# quad_probability_gate.net
KiCad netlist of a schematic drawn in EAGLE
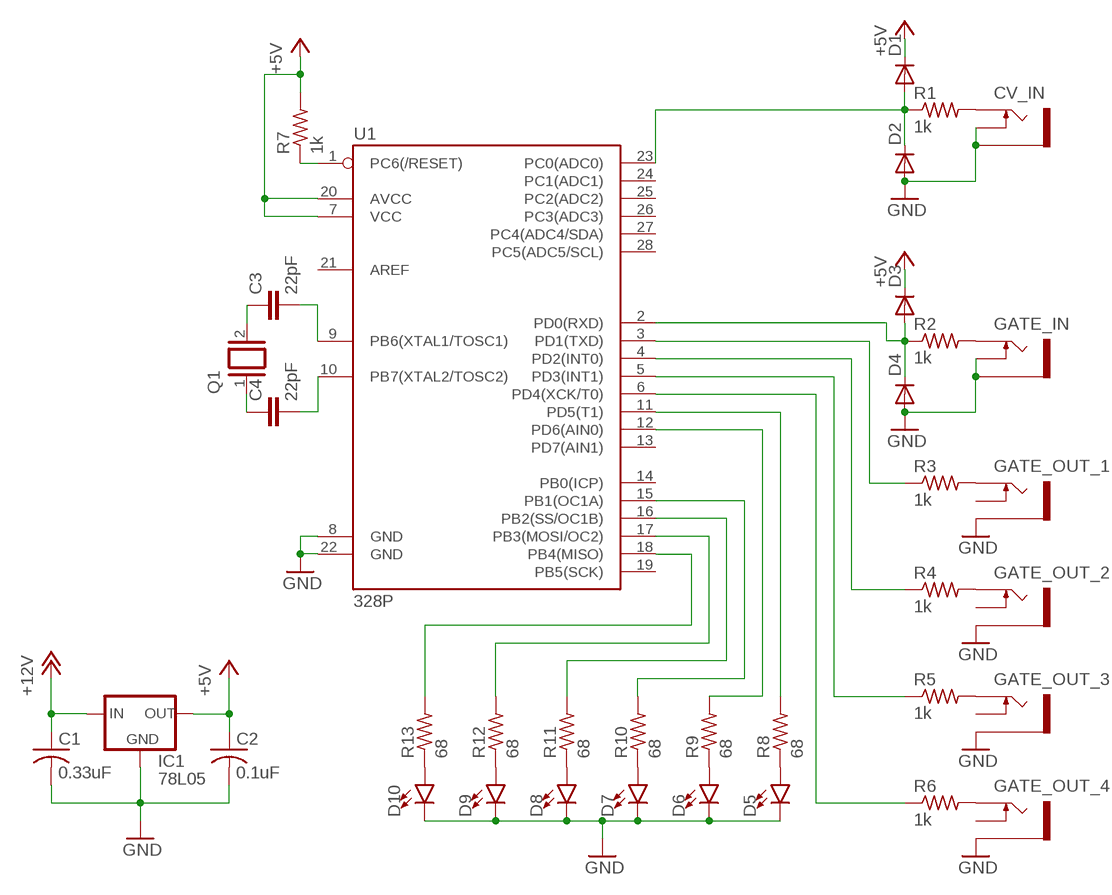
[diagram p0: schematic, sheet 1]

(export (version "E")
  (design (tool "Eeschema 10.0.6"))
  (components
    (comp (ref "C1")
      (value "0.33uF")
      (footprint "eagle-import:C025-024X044")
      (libsource (lib "eagle-import") (part "C-US025-024X044"))
    )
    (comp (ref "C2")
      (value "0.1uF")
      (footprint "eagle-import:C025-024X044")
      (libsource (lib "eagle-import") (part "C-US025-024X044"))
    )
    (comp (ref "C3")
      (value "22pF")
      (footprint "eagle-import:0603")
      (libsource (lib "eagle-import") (part "22PF-0603-50V-5%"))
    )
    (comp (ref "C4")
      (value "22pF")
      (footprint "eagle-import:0603")
      (libsource (lib "eagle-import") (part "22PF-0603-50V-5%"))
    )
    (comp (ref "CV_IN")
      (value "THONKICONNOLD")
      (footprint "eagle-import:THONKICONN")
      (libsource (lib "eagle-import") (part "THONKICONNOLD"))
    )
    (comp (ref "D1")
      (value "SMALL_DIODEDO35-7")
      (footprint "eagle-import:DO35-7")
      (libsource (lib "eagle-import") (part "SMALL_DIODEDO35-7"))
    )
    (comp (ref "D2")
      (value "SMALL_DIODEDO35-7")
      (footprint "eagle-import:DO35-7")
      (libsource (lib "eagle-import") (part "SMALL_DIODEDO35-7"))
    )
    (comp (ref "D3")
      (value "SMALL_DIODEDO35-7")
      (footprint "eagle-import:DO35-7")
      (libsource (lib "eagle-import") (part "SMALL_DIODEDO35-7"))
    )
    (comp (ref "D4")
      (value "SMALL_DIODEDO35-7")
      (footprint "eagle-import:DO35-7")
      (libsource (lib "eagle-import") (part "SMALL_DIODEDO35-7"))
    )
    (comp (ref "D5")
      (value "LED-3MM-NO_SILK")
      (footprint "eagle-import:LED_3MM-NS")
      (libsource (lib "eagle-import") (part "LED-3MM-NO_SILK"))
    )
    (comp (ref "D6")
      (value "LED-3MM-NO_SILK")
      (footprint "eagle-import:LED_3MM-NS")
      (libsource (lib "eagle-import") (part "LED-3MM-NO_SILK"))
    )
    (comp (ref "D7")
      (value "LED-3MM-NO_SILK")
      (footprint "eagle-import:LED_3MM-NS")
      (libsource (lib "eagle-import") (part "LED-3MM-NO_SILK"))
    )
    (comp (ref "D8")
      (value "LED-3MM-NO_SILK")
      (footprint "eagle-import:LED_3MM-NS")
      (libsource (lib "eagle-import") (part "LED-3MM-NO_SILK"))
    )
    (comp (ref "D9")
      (value "LED-3MM-NO_SILK")
      (footprint "eagle-import:LED_3MM-NS")
      (libsource (lib "eagle-import") (part "LED-3MM-NO_SILK"))
    )
    (comp (ref "D10")
      (value "LED-3MM-NO_SILK")
      (footprint "eagle-import:LED_3MM-NS")
      (libsource (lib "eagle-import") (part "LED-3MM-NO_SILK"))
    )
    (comp (ref "GATE_IN")
      (value "THONKICONNOLD")
      (footprint "eagle-import:THONKICONN")
      (libsource (lib "eagle-import") (part "THONKICONNOLD"))
    )
    (comp (ref "GATE_OUT_1")
      (value "THONKICONNOLD")
      (footprint "eagle-import:THONKICONN")
      (libsource (lib "eagle-import") (part "THONKICONNOLD"))
    )
    (comp (ref "GATE_OUT_2")
      (value "THONKICONNOLD")
      (footprint "eagle-import:THONKICONN")
      (libsource (lib "eagle-import") (part "THONKICONNOLD"))
    )
    (comp (ref "GATE_OUT_3")
      (value "THONKICONNOLD")
      (footprint "eagle-import:THONKICONN")
      (libsource (lib "eagle-import") (part "THONKICONNOLD"))
    )
    (comp (ref "GATE_OUT_4")
      (value "THONKICONNOLD")
      (footprint "eagle-import:THONKICONN")
      (libsource (lib "eagle-import") (part "THONKICONNOLD"))
    )
    (comp (ref "IC1")
      (value "78L05")
      (footprint "eagle-import:78LXX")
      (libsource (lib "eagle-import") (part "78LXX"))
    )
    (comp (ref "Q1")
      (value "XTAL")
      (footprint "eagle-import:Q")
      (libsource (lib "eagle-import") (part "XTAL"))
    )
    (comp (ref "R1")
      (value "1k")
      (footprint "eagle-import:0204V")
      (libsource (lib "eagle-import") (part "R-US_0204/2V"))
    )
    (comp (ref "R2")
      (value "1k")
      (footprint "eagle-import:0204V")
      (libsource (lib "eagle-import") (part "R-US_0204/2V"))
    )
    (comp (ref "R3")
      (value "1k")
      (footprint "eagle-import:0204V")
      (libsource (lib "eagle-import") (part "R-US_0204/2V"))
    )
    (comp (ref "R4")
      (value "1k")
      (footprint "eagle-import:0204V")
      (libsource (lib "eagle-import") (part "R-US_0204/2V"))
    )
    (comp (ref "R5")
      (value "1k")
      (footprint "eagle-import:0204V")
      (libsource (lib "eagle-import") (part "R-US_0204/2V"))
    )
    (comp (ref "R6")
      (value "1k")
      (footprint "eagle-import:0204V")
      (libsource (lib "eagle-import") (part "R-US_0204/2V"))
    )
    (comp (ref "R7")
      (value "1k")
      (footprint "eagle-import:0204V")
      (libsource (lib "eagle-import") (part "R-US_0204/2V"))
    )
    (comp (ref "R8")
      (value "68")
      (footprint "eagle-import:0204V")
      (libsource (lib "eagle-import") (part "R-US_0204/2V"))
    )
    (comp (ref "R9")
      (value "68")
      (footprint "eagle-import:0204V")
      (libsource (lib "eagle-import") (part "R-US_0204/2V"))
    )
    (comp (ref "R10")
      (value "68")
      (footprint "eagle-import:0204V")
      (libsource (lib "eagle-import") (part "R-US_0204/2V"))
    )
    (comp (ref "R11")
      (value "68")
      (footprint "eagle-import:0204V")
      (libsource (lib "eagle-import") (part "R-US_0204/2V"))
    )
    (comp (ref "R12")
      (value "68")
      (footprint "eagle-import:0204V")
      (libsource (lib "eagle-import") (part "R-US_0204/2V"))
    )
    (comp (ref "R13")
      (value "68")
      (footprint "eagle-import:0204V")
      (libsource (lib "eagle-import") (part "R-US_0204/2V"))
    )
    (comp (ref "U1")
      (value "328P")
      (footprint "eagle-import:DIP28")
      (libsource (lib "eagle-import") (part "ATMEGA328P_PDIP"))
    )
  )
  (nets
    (net (code "1") (name "+5V") (class "Default")
      (node (ref "C2") (pin "1") (pinfunction "1_1") (pintype "passive"))
      (node (ref "D1") (pin "C") (pinfunction "C_C") (pintype "passive"))
      (node (ref "D3") (pin "C") (pinfunction "C_C") (pintype "passive"))
      (node (ref "IC1") (pin "OUT") (pinfunction "OUT_OUT") (pintype "passive"))
      (node (ref "R7") (pin "2") (pinfunction "2_2") (pintype "passive"))
      (node (ref "U1") (pin "20") (pinfunction "AVCC_20") (pintype "bidirectional"))
      (node (ref "U1") (pin "7") (pinfunction "VCC_7") (pintype "bidirectional"))
    )
    (net (code "2") (name "+12V") (class "Default")
      (node (ref "C1") (pin "1") (pinfunction "1_1") (pintype "passive"))
      (node (ref "IC1") (pin "IN") (pinfunction "IN_IN") (pintype "input"))
    )
    (net (code "3") (name "GND") (class "Default")
      (node (ref "C1") (pin "2") (pinfunction "2_2") (pintype "passive"))
      (node (ref "C2") (pin "2") (pinfunction "2_2") (pintype "passive"))
      (node (ref "CV_IN") (pin "P$1_SLEEVE") (pinfunction "SLEEVE_P$1_SLEEVE") (pintype "passive"))
      (node (ref "CV_IN") (pin "P$2_SWITCH") (pinfunction "SWITCH_P$2_SWITCH") (pintype "passive"))
      (node (ref "D10") (pin "K") (pinfunction "C_K") (pintype "passive"))
      (node (ref "D2") (pin "A") (pinfunction "A_A") (pintype "passive"))
      (node (ref "D4") (pin "A") (pinfunction "A_A") (pintype "passive"))
      (node (ref "D5") (pin "K") (pinfunction "C_K") (pintype "passive"))
      (node (ref "D6") (pin "K") (pinfunction "C_K") (pintype "passive"))
      (node (ref "D7") (pin "K") (pinfunction "C_K") (pintype "passive"))
      (node (ref "D8") (pin "K") (pinfunction "C_K") (pintype "passive"))
      (node (ref "D9") (pin "K") (pinfunction "C_K") (pintype "passive"))
      (node (ref "GATE_IN") (pin "P$1_SLEEVE") (pinfunction "SLEEVE_P$1_SLEEVE") (pintype "passive"))
      (node (ref "GATE_IN") (pin "P$2_SWITCH") (pinfunction "SWITCH_P$2_SWITCH") (pintype "passive"))
      (node (ref "GATE_OUT_1") (pin "P$1_SLEEVE") (pinfunction "SLEEVE_P$1_SLEEVE") (pintype "passive"))
      (node (ref "GATE_OUT_2") (pin "P$1_SLEEVE") (pinfunction "SLEEVE_P$1_SLEEVE") (pintype "passive"))
      (node (ref "GATE_OUT_3") (pin "P$1_SLEEVE") (pinfunction "SLEEVE_P$1_SLEEVE") (pintype "passive"))
      (node (ref "GATE_OUT_4") (pin "P$1_SLEEVE") (pinfunction "SLEEVE_P$1_SLEEVE") (pintype "passive"))
      (node (ref "IC1") (pin "GND") (pinfunction "GND_GND") (pintype "input"))
      (node (ref "U1") (pin "22") (pinfunction "GND_22") (pintype "bidirectional"))
      (node (ref "U1") (pin "8") (pinfunction "GND_8") (pintype "bidirectional"))
    )
    (net (code "4") (name "Net-(C3-Pad1)") (class "Default")
      (node (ref "C3") (pin "1") (pinfunction "1_1") (pintype "passive"))
      (node (ref "Q1") (pin "2") (pinfunction "2_2") (pintype "passive"))
    )
    (net (code "5") (name "Net-(C4-Pad1)") (class "Default")
      (node (ref "C4") (pin "1") (pinfunction "1_1") (pintype "passive"))
      (node (ref "Q1") (pin "1") (pinfunction "1_1") (pintype "passive"))
    )
    (net (code "6") (name "Net-(CV_IN-TIP)") (class "Default")
      (node (ref "CV_IN") (pin "P$3_TIP") (pinfunction "TIP_P$3_TIP") (pintype "passive"))
      (node (ref "R1") (pin "2") (pinfunction "2_2") (pintype "passive"))
    )
    (net (code "7") (name "Net-(D5-PadA)") (class "Default")
      (node (ref "D5") (pin "A") (pinfunction "A_A") (pintype "passive"))
      (node (ref "R8") (pin "1") (pinfunction "1_1") (pintype "passive"))
    )
    (net (code "8") (name "Net-(D6-PadA)") (class "Default")
      (node (ref "D6") (pin "A") (pinfunction "A_A") (pintype "passive"))
      (node (ref "R9") (pin "1") (pinfunction "1_1") (pintype "passive"))
    )
    (net (code "9") (name "Net-(D7-PadA)") (class "Default")
      (node (ref "D7") (pin "A") (pinfunction "A_A") (pintype "passive"))
      (node (ref "R10") (pin "1") (pinfunction "1_1") (pintype "passive"))
    )
    (net (code "10") (name "Net-(D8-PadA)") (class "Default")
      (node (ref "D8") (pin "A") (pinfunction "A_A") (pintype "passive"))
      (node (ref "R11") (pin "1") (pinfunction "1_1") (pintype "passive"))
    )
    (net (code "11") (name "Net-(D9-PadA)") (class "Default")
      (node (ref "D9") (pin "A") (pinfunction "A_A") (pintype "passive"))
      (node (ref "R12") (pin "1") (pinfunction "1_1") (pintype "passive"))
    )
    (net (code "12") (name "Net-(D10-PadA)") (class "Default")
      (node (ref "D10") (pin "A") (pinfunction "A_A") (pintype "passive"))
      (node (ref "R13") (pin "1") (pinfunction "1_1") (pintype "passive"))
    )
    (net (code "13") (name "Net-(GATE_IN-TIP)") (class "Default")
      (node (ref "GATE_IN") (pin "P$3_TIP") (pinfunction "TIP_P$3_TIP") (pintype "passive"))
      (node (ref "R2") (pin "2") (pinfunction "2_2") (pintype "passive"))
    )
    (net (code "14") (name "Net-(GATE_OUT_1-TIP)") (class "Default")
      (node (ref "GATE_OUT_1") (pin "P$3_TIP") (pinfunction "TIP_P$3_TIP") (pintype "passive"))
      (node (ref "R3") (pin "2") (pinfunction "2_2") (pintype "passive"))
    )
    (net (code "15") (name "Net-(GATE_OUT_2-TIP)") (class "Default")
      (node (ref "GATE_OUT_2") (pin "P$3_TIP") (pinfunction "TIP_P$3_TIP") (pintype "passive"))
      (node (ref "R4") (pin "2") (pinfunction "2_2") (pintype "passive"))
    )
    (net (code "16") (name "Net-(GATE_OUT_3-TIP)") (class "Default")
      (node (ref "GATE_OUT_3") (pin "P$3_TIP") (pinfunction "TIP_P$3_TIP") (pintype "passive"))
      (node (ref "R5") (pin "2") (pinfunction "2_2") (pintype "passive"))
    )
    (net (code "17") (name "Net-(GATE_OUT_4-TIP)") (class "Default")
      (node (ref "GATE_OUT_4") (pin "P$3_TIP") (pinfunction "TIP_P$3_TIP") (pintype "passive"))
      (node (ref "R6") (pin "2") (pinfunction "2_2") (pintype "passive"))
    )
    (net (code "18") (name "Net-(U1-PB1(OC1A))") (class "Default")
      (node (ref "R10") (pin "2") (pinfunction "2_2") (pintype "passive"))
      (node (ref "U1") (pin "15") (pinfunction "PB1(OC1A)_15") (pintype "bidirectional"))
    )
    (net (code "19") (name "Net-(U1-PB2(SS{slash}OC1B))") (class "Default")
      (node (ref "R11") (pin "2") (pinfunction "2_2") (pintype "passive"))
      (node (ref "U1") (pin "16") (pinfunction "PB2(SS/OC1B)_16") (pintype "bidirectional"))
    )
    (net (code "20") (name "Net-(U1-PB3(MOSI{slash}OC2))") (class "Default")
      (node (ref "R12") (pin "2") (pinfunction "2_2") (pintype "passive"))
      (node (ref "U1") (pin "17") (pinfunction "PB3(MOSI/OC2)_17") (pintype "bidirectional"))
    )
    (net (code "21") (name "Net-(U1-PB4(MISO))") (class "Default")
      (node (ref "R13") (pin "2") (pinfunction "2_2") (pintype "passive"))
      (node (ref "U1") (pin "18") (pinfunction "PB4(MISO)_18") (pintype "bidirectional"))
    )
    (net (code "22") (name "Net-(U1-PB6(XTAL1{slash}TOSC1))") (class "Default")
      (node (ref "C3") (pin "2") (pinfunction "2_2") (pintype "passive"))
      (node (ref "U1") (pin "9") (pinfunction "PB6(XTAL1/TOSC1)_9") (pintype "bidirectional"))
    )
    (net (code "23") (name "Net-(U1-PB7(XTAL2{slash}TOSC2))") (class "Default")
      (node (ref "C4") (pin "2") (pinfunction "2_2") (pintype "passive"))
      (node (ref "U1") (pin "10") (pinfunction "PB7(XTAL2/TOSC2)_10") (pintype "bidirectional"))
    )
    (net (code "24") (name "Net-(U1-PC0(ADC0))") (class "Default")
      (node (ref "D1") (pin "A") (pinfunction "A_A") (pintype "passive"))
      (node (ref "D2") (pin "C") (pinfunction "C_C") (pintype "passive"))
      (node (ref "R1") (pin "1") (pinfunction "1_1") (pintype "passive"))
      (node (ref "U1") (pin "23") (pinfunction "PC0(ADC0)_23") (pintype "bidirectional"))
    )
    (net (code "25") (name "Net-(U1-PC6({slash}RESET))") (class "Default")
      (node (ref "R7") (pin "1") (pinfunction "1_1") (pintype "passive"))
      (node (ref "U1") (pin "1") (pinfunction "PC6(/RESET)_1") (pintype "bidirectional"))
    )
    (net (code "26") (name "Net-(U1-PD0(RXD))") (class "Default")
      (node (ref "D3") (pin "A") (pinfunction "A_A") (pintype "passive"))
      (node (ref "D4") (pin "C") (pinfunction "C_C") (pintype "passive"))
      (node (ref "R2") (pin "1") (pinfunction "1_1") (pintype "passive"))
      (node (ref "U1") (pin "2") (pinfunction "PD0(RXD)_2") (pintype "bidirectional"))
    )
    (net (code "27") (name "Net-(U1-PD1(TXD))") (class "Default")
      (node (ref "R3") (pin "1") (pinfunction "1_1") (pintype "passive"))
      (node (ref "U1") (pin "3") (pinfunction "PD1(TXD)_3") (pintype "bidirectional"))
    )
    (net (code "28") (name "Net-(U1-PD2(INT0))") (class "Default")
      (node (ref "R4") (pin "1") (pinfunction "1_1") (pintype "passive"))
      (node (ref "U1") (pin "4") (pinfunction "PD2(INT0)_4") (pintype "bidirectional"))
    )
    (net (code "29") (name "Net-(U1-PD3(INT1))") (class "Default")
      (node (ref "R5") (pin "1") (pinfunction "1_1") (pintype "passive"))
      (node (ref "U1") (pin "5") (pinfunction "PD3(INT1)_5") (pintype "bidirectional"))
    )
    (net (code "30") (name "Net-(U1-PD4(XCK{slash}T0))") (class "Default")
      (node (ref "R6") (pin "1") (pinfunction "1_1") (pintype "passive"))
      (node (ref "U1") (pin "6") (pinfunction "PD4(XCK/T0)_6") (pintype "bidirectional"))
    )
    (net (code "31") (name "Net-(U1-PD5(T1))") (class "Default")
      (node (ref "R8") (pin "2") (pinfunction "2_2") (pintype "passive"))
      (node (ref "U1") (pin "11") (pinfunction "PD5(T1)_11") (pintype "bidirectional"))
    )
    (net (code "32") (name "Net-(U1-PD6(AIN0))") (class "Default")
      (node (ref "R9") (pin "2") (pinfunction "2_2") (pintype "passive"))
      (node (ref "U1") (pin "12") (pinfunction "PD6(AIN0)_12") (pintype "bidirectional"))
    )
    (net (code "33") (name "unconnected-(GATE_OUT_1-SWITCH-PadP$2_SWITCH)") (class "Default")
      (node (ref "GATE_OUT_1") (pin "P$2_SWITCH") (pinfunction "SWITCH_P$2_SWITCH") (pintype "passive"))
    )
    (net (code "34") (name "unconnected-(GATE_OUT_2-SWITCH-PadP$2_SWITCH)") (class "Default")
      (node (ref "GATE_OUT_2") (pin "P$2_SWITCH") (pinfunction "SWITCH_P$2_SWITCH") (pintype "passive"))
    )
    (net (code "35") (name "unconnected-(GATE_OUT_3-SWITCH-PadP$2_SWITCH)") (class "Default")
      (node (ref "GATE_OUT_3") (pin "P$2_SWITCH") (pinfunction "SWITCH_P$2_SWITCH") (pintype "passive"))
    )
    (net (code "36") (name "unconnected-(GATE_OUT_4-SWITCH-PadP$2_SWITCH)") (class "Default")
      (node (ref "GATE_OUT_4") (pin "P$2_SWITCH") (pinfunction "SWITCH_P$2_SWITCH") (pintype "passive"))
    )
    (net (code "37") (name "unconnected-(U1-AREF-Pad21)") (class "Default")
      (node (ref "U1") (pin "21") (pinfunction "AREF_21") (pintype "bidirectional"))
    )
    (net (code "38") (name "unconnected-(U1-PB0(ICP)-Pad14)") (class "Default")
      (node (ref "U1") (pin "14") (pinfunction "PB0(ICP)_14") (pintype "bidirectional"))
    )
    (net (code "39") (name "unconnected-(U1-PB5(SCK)-Pad19)") (class "Default")
      (node (ref "U1") (pin "19") (pinfunction "PB5(SCK)_19") (pintype "bidirectional"))
    )
    (net (code "40") (name "unconnected-(U1-PC1(ADC1)-Pad24)") (class "Default")
      (node (ref "U1") (pin "24") (pinfunction "PC1(ADC1)_24") (pintype "bidirectional"))
    )
    (net (code "41") (name "unconnected-(U1-PC2(ADC2)-Pad25)") (class "Default")
      (node (ref "U1") (pin "25") (pinfunction "PC2(ADC2)_25") (pintype "bidirectional"))
    )
    (net (code "42") (name "unconnected-(U1-PC3(ADC3)-Pad26)") (class "Default")
      (node (ref "U1") (pin "26") (pinfunction "PC3(ADC3)_26") (pintype "bidirectional"))
    )
    (net (code "43") (name "unconnected-(U1-PC4(ADC4{slash}SDA)-Pad27)") (class "Default")
      (node (ref "U1") (pin "27") (pinfunction "PC4(ADC4/SDA)_27") (pintype "bidirectional"))
    )
    (net (code "44") (name "unconnected-(U1-PC5(ADC5{slash}SCL)-Pad28)") (class "Default")
      (node (ref "U1") (pin "28") (pinfunction "PC5(ADC5/SCL)_28") (pintype "bidirectional"))
    )
    (net (code "45") (name "unconnected-(U1-PD7(AIN1)-Pad13)") (class "Default")
      (node (ref "U1") (pin "13") (pinfunction "PD7(AIN1)_13") (pintype "bidirectional"))
    )
  )
)
